# el_de_nosotros.net
KiCad netlist of a schematic drawn in EAGLE
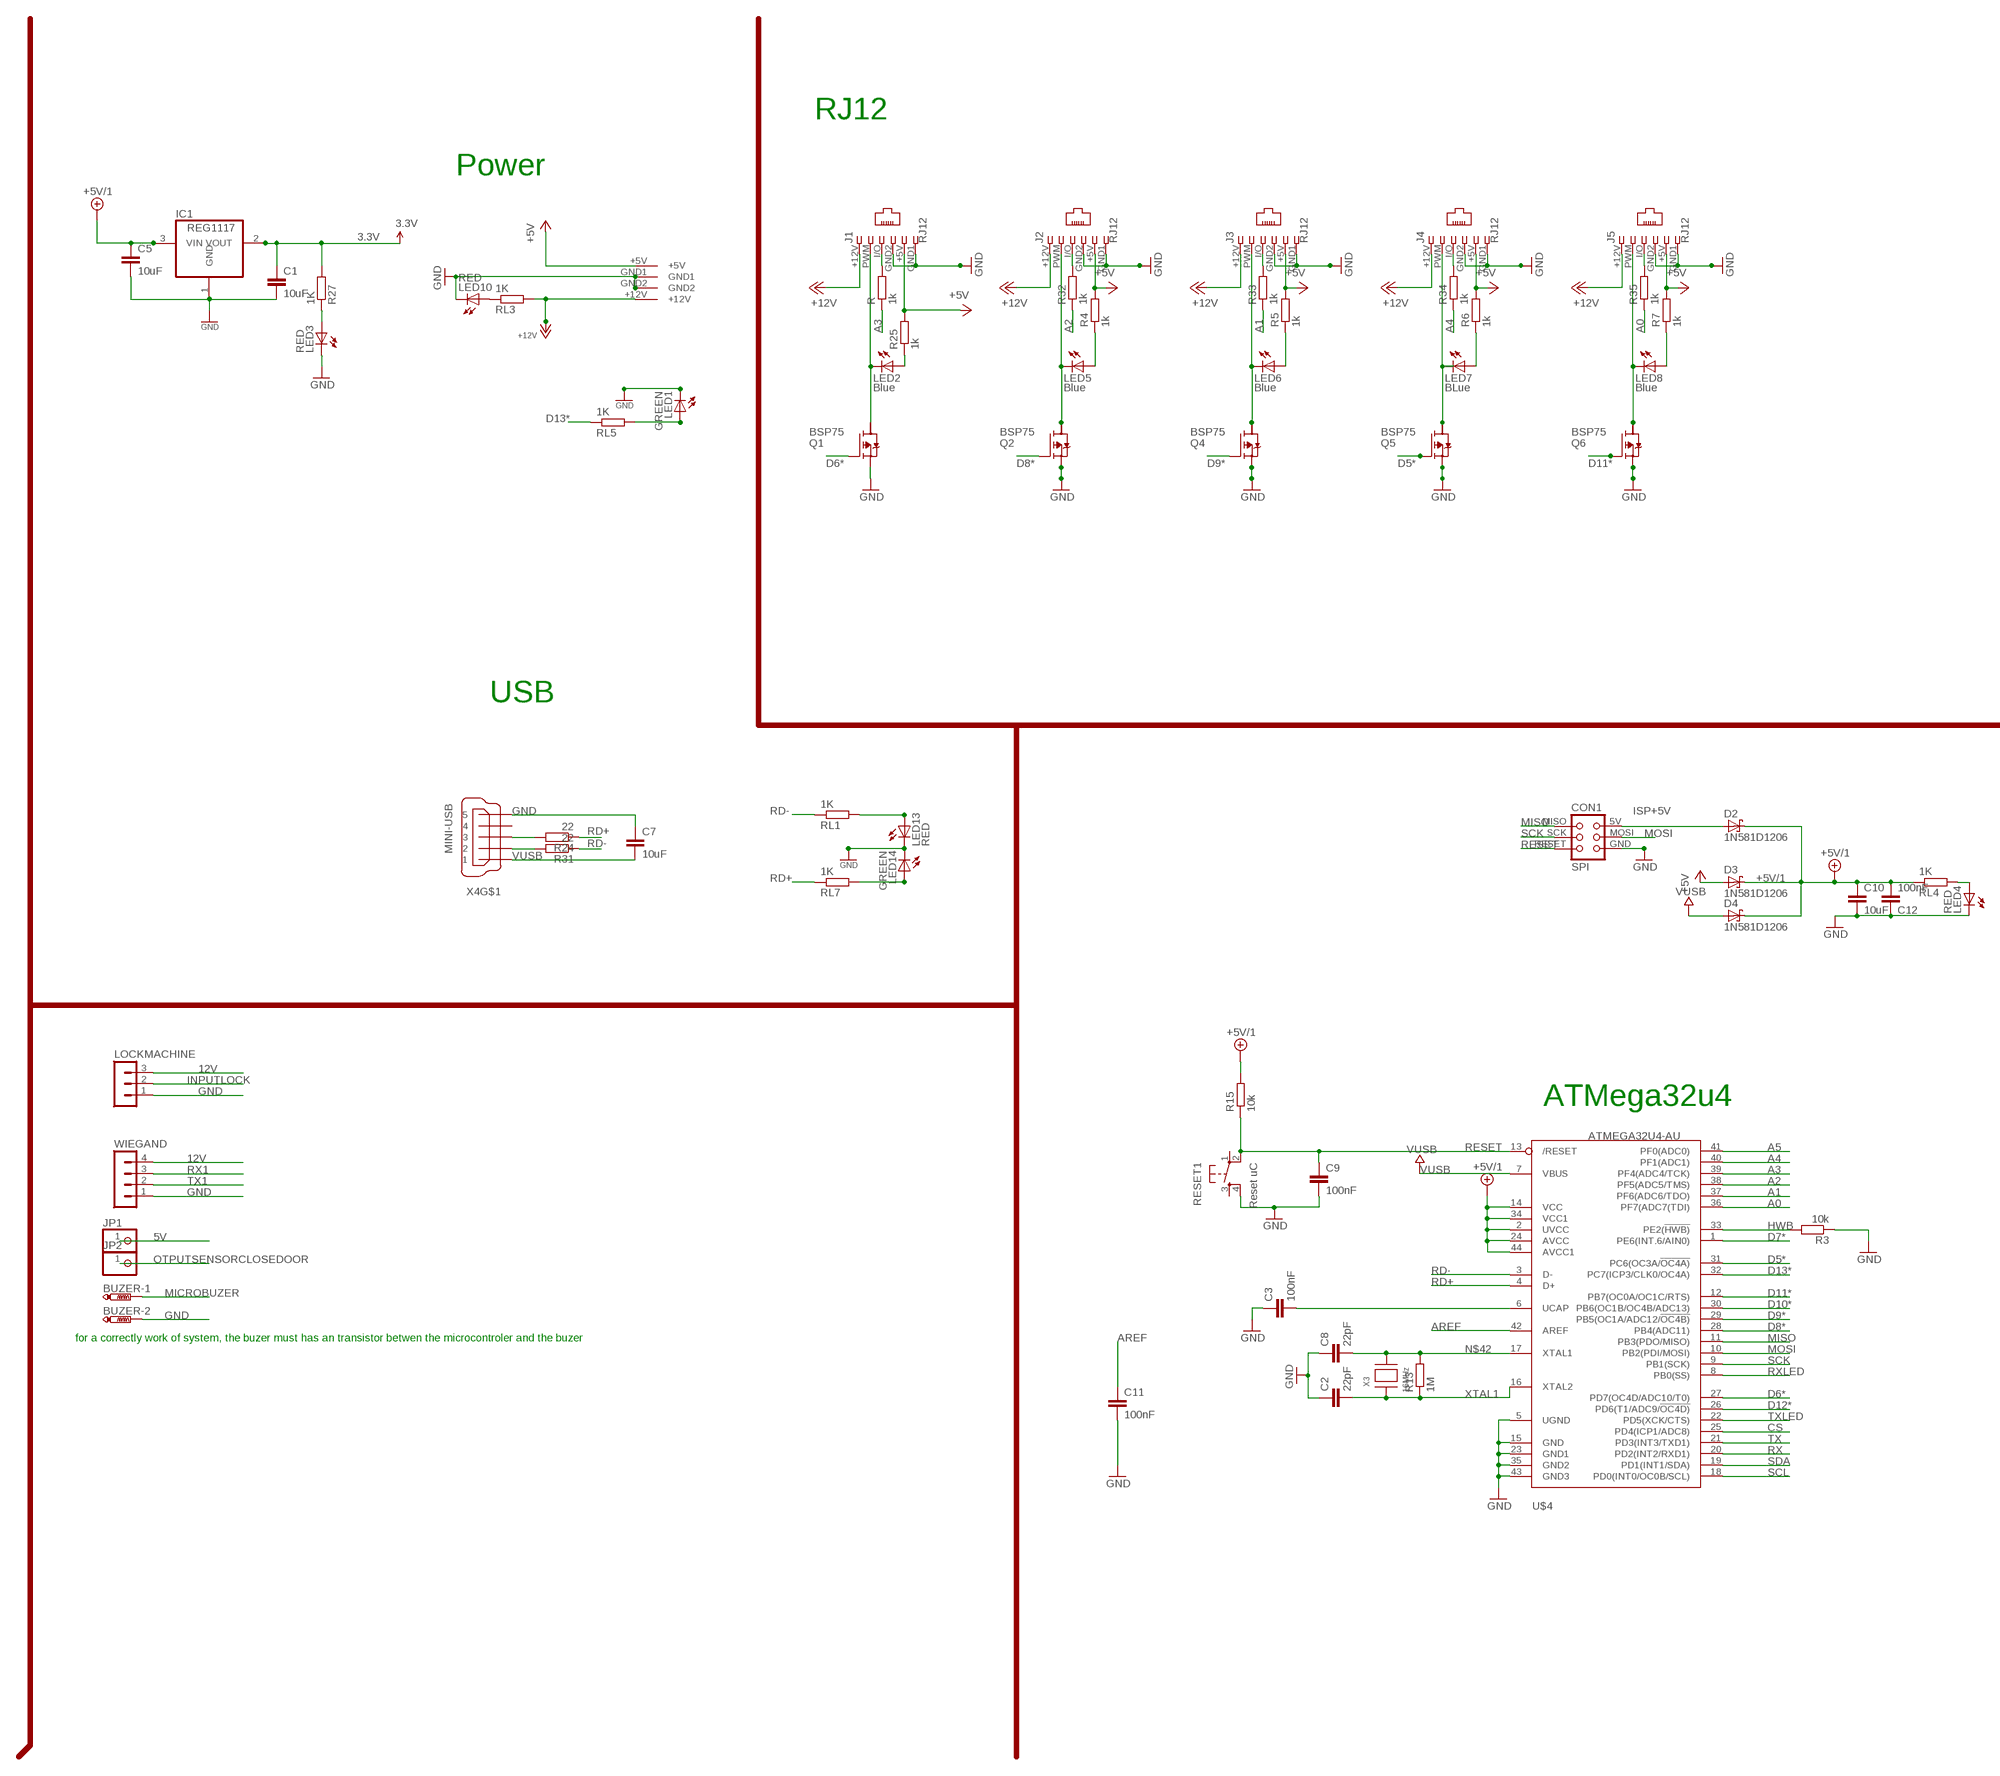
[diagram p0: schematic, sheet 1, part 1 of 2]
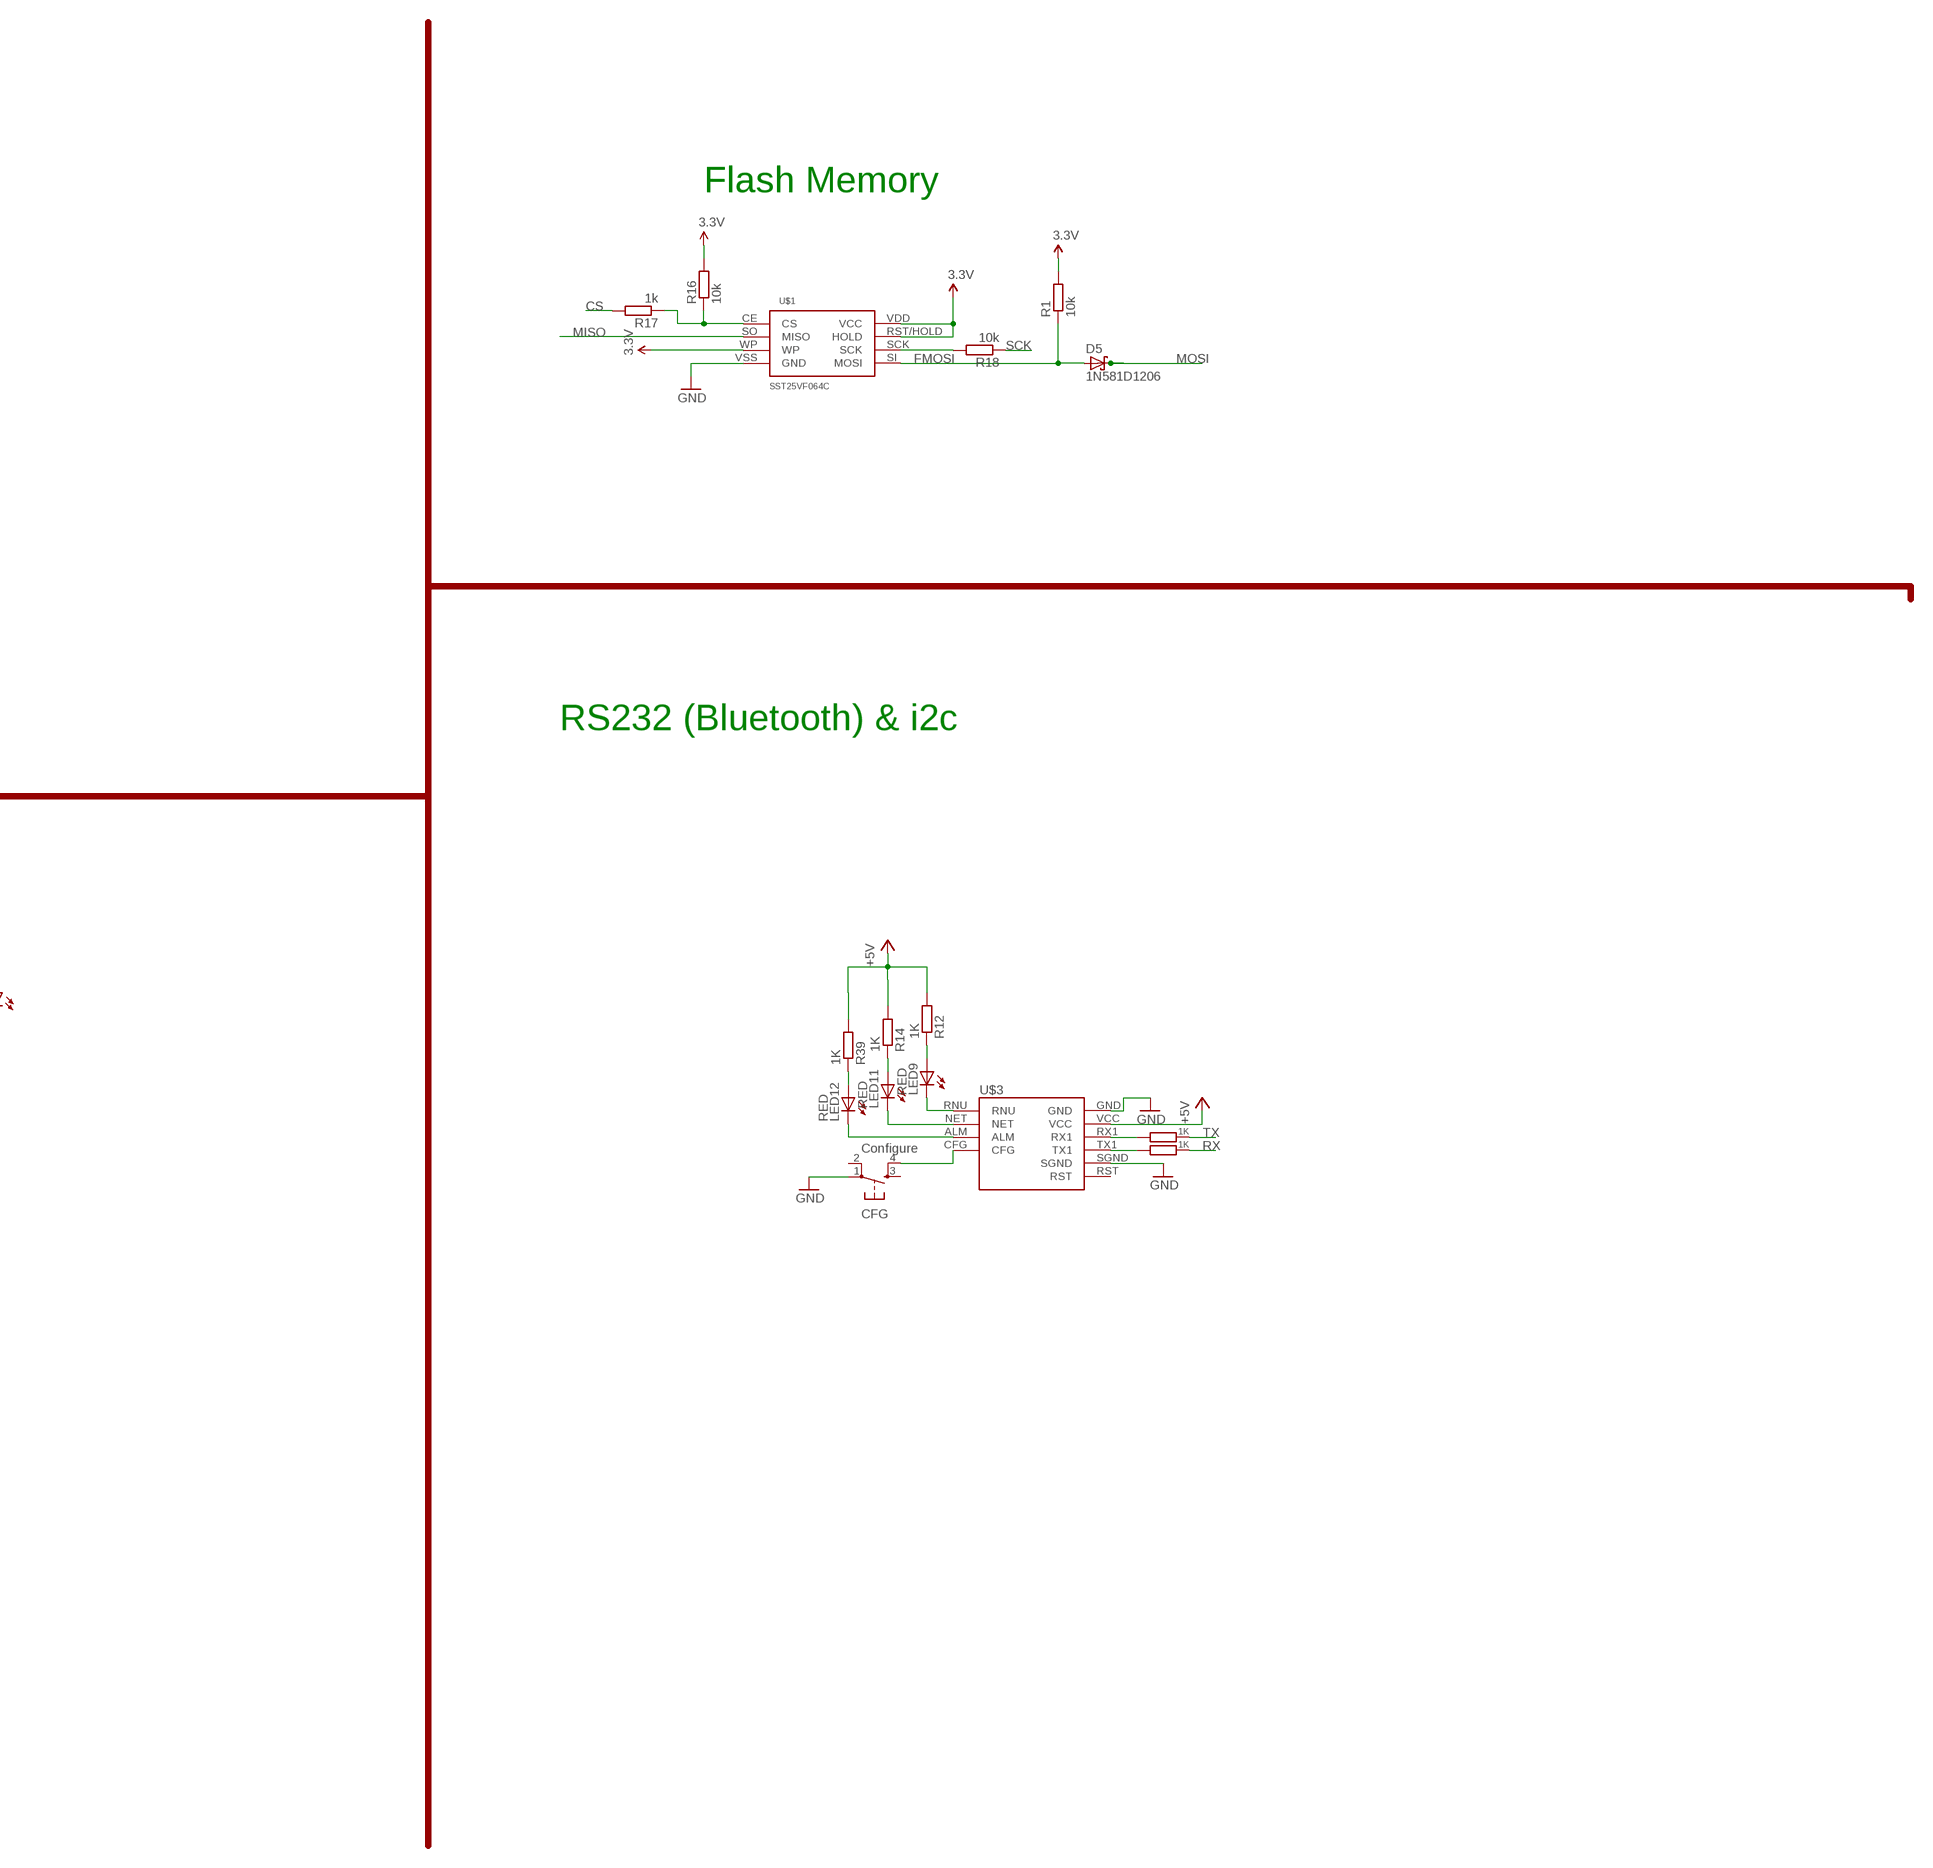
[diagram p1: schematic, sheet 1, part 2 of 2]

(export (version "E")
  (design (tool "Eeschema 10.0.6"))
  (components
    (comp (ref "BUZER")
      (value "PTR2")
      (footprint "eagle-import:P2-38-17")
      (libsource (lib "eagle-import") (part "PTR2"))
    )
    (comp (ref "C1")
      (value "10uF")
      (footprint "eagle-import:C1206")
      (libsource (lib "eagle-import") (part "C-EUC1206"))
    )
    (comp (ref "C2")
      (value "22pF")
      (footprint "eagle-import:C1206")
      (libsource (lib "eagle-import") (part "C-EUC1206"))
    )
    (comp (ref "C3")
      (value "100nF")
      (footprint "eagle-import:C1206")
      (libsource (lib "eagle-import") (part "C-EUC1206"))
    )
    (comp (ref "C5")
      (value "10uF")
      (footprint "eagle-import:C1206")
      (libsource (lib "eagle-import") (part "C-EUC1206"))
    )
    (comp (ref "C7")
      (value "10uF")
      (footprint "eagle-import:C1206")
      (libsource (lib "eagle-import") (part "C-EUC1206"))
    )
    (comp (ref "C8")
      (value "22pF")
      (footprint "eagle-import:C1206")
      (libsource (lib "eagle-import") (part "C-EUC1206"))
    )
    (comp (ref "C9")
      (value "100nF")
      (footprint "eagle-import:C1206")
      (libsource (lib "eagle-import") (part "C-EUC1206"))
    )
    (comp (ref "C10")
      (value "10uF")
      (footprint "eagle-import:C1206")
      (libsource (lib "eagle-import") (part "C-EUC1206"))
    )
    (comp (ref "C11")
      (value "100nF")
      (footprint "eagle-import:C1206")
      (libsource (lib "eagle-import") (part "C-EUC1206"))
    )
    (comp (ref "C12")
      (value "100nF")
      (footprint "eagle-import:C1206")
      (libsource (lib "eagle-import") (part "C-EUC1206"))
    )
    (comp (ref "CFG")
      (value "Configure")
      (footprint "eagle-import:TACTILE_SWITCH_SMD")
      (libsource (lib "eagle-import") (part "TAC_SWITCHSMD"))
    )
    (comp (ref "CON1")
      (value "SPI")
      (footprint "eagle-import:TC2030-MCP-NL")
      (libsource (lib "eagle-import") (part "TINYISPT"))
    )
    (comp (ref "D2")
      (value "1N581D1206")
      (footprint "eagle-import:LED-1206")
      (libsource (lib "eagle-import") (part "1N581D1206"))
    )
    (comp (ref "D3")
      (value "1N581D1206")
      (footprint "eagle-import:LED-1206")
      (libsource (lib "eagle-import") (part "1N581D1206"))
    )
    (comp (ref "D4")
      (value "1N581D1206")
      (footprint "eagle-import:LED-1206")
      (libsource (lib "eagle-import") (part "1N581D1206"))
    )
    (comp (ref "D5")
      (value "1N581D1206")
      (footprint "eagle-import:LED-1206")
      (libsource (lib "eagle-import") (part "1N581D1206"))
    )
    (comp (ref "IC1")
      (value "REG1117")
      (footprint "eagle-import:SOT223")
      (libsource (lib "eagle-import") (part "REG1117"))
    )
    (comp (ref "J1")
      (value "RJ12")
      (footprint "eagle-import:RJ12-STRAIGHT")
      (libsource (lib "eagle-import") (part "RJ12STRAIGHT"))
    )
    (comp (ref "J2")
      (value "RJ12")
      (footprint "eagle-import:RJ12-STRAIGHT")
      (libsource (lib "eagle-import") (part "RJ12STRAIGHT"))
    )
    (comp (ref "J3")
      (value "RJ12")
      (footprint "eagle-import:RJ12-STRAIGHT")
      (libsource (lib "eagle-import") (part "RJ12STRAIGHT"))
    )
    (comp (ref "J4")
      (value "RJ12")
      (footprint "eagle-import:RJ12-STRAIGHT")
      (libsource (lib "eagle-import") (part "RJ12STRAIGHT"))
    )
    (comp (ref "J5")
      (value "RJ12")
      (footprint "eagle-import:RJ12-STRAIGHT")
      (libsource (lib "eagle-import") (part "RJ12STRAIGHT"))
    )
    (comp (ref "JP1")
      (value "PINHD-1X1")
      (footprint "eagle-import:1X01")
      (libsource (lib "eagle-import") (part "PINHD-1X1"))
    )
    (comp (ref "JP2")
      (value "PINHD-1X1")
      (footprint "eagle-import:1X01")
      (libsource (lib "eagle-import") (part "PINHD-1X1"))
    )
    (comp (ref "LED1")
      (value "GREEN")
      (footprint "eagle-import:CHIPLED_1206")
      (libsource (lib "eagle-import") (part "LEDCHIPLED_1206"))
    )
    (comp (ref "LED2")
      (value "Blue")
      (footprint "eagle-import:CHIPLED_1206")
      (libsource (lib "eagle-import") (part "LEDCHIPLED_1206"))
    )
    (comp (ref "LED3")
      (value "RED")
      (footprint "eagle-import:CHIPLED_1206")
      (libsource (lib "eagle-import") (part "LEDCHIPLED_1206"))
    )
    (comp (ref "LED4")
      (value "RED")
      (footprint "eagle-import:CHIPLED_1206")
      (libsource (lib "eagle-import") (part "LEDCHIPLED_1206"))
    )
    (comp (ref "LED5")
      (value "Blue")
      (footprint "eagle-import:CHIPLED_1206")
      (libsource (lib "eagle-import") (part "LEDCHIPLED_1206"))
    )
    (comp (ref "LED6")
      (value "Blue")
      (footprint "eagle-import:CHIPLED_1206")
      (libsource (lib "eagle-import") (part "LEDCHIPLED_1206"))
    )
    (comp (ref "LED7")
      (value "BLue")
      (footprint "eagle-import:CHIPLED_1206")
      (libsource (lib "eagle-import") (part "LEDCHIPLED_1206"))
    )
    (comp (ref "LED8")
      (value "Blue")
      (footprint "eagle-import:CHIPLED_1206")
      (libsource (lib "eagle-import") (part "LEDCHIPLED_1206"))
    )
    (comp (ref "LED9")
      (value "RED")
      (footprint "eagle-import:CHIPLED_1206")
      (libsource (lib "eagle-import") (part "LEDCHIPLED_1206"))
    )
    (comp (ref "LED10")
      (value "RED")
      (footprint "eagle-import:CHIPLED_1206")
      (libsource (lib "eagle-import") (part "LEDCHIPLED_1206"))
    )
    (comp (ref "LED11")
      (value "RED")
      (footprint "eagle-import:CHIPLED_1206")
      (libsource (lib "eagle-import") (part "LEDCHIPLED_1206"))
    )
    (comp (ref "LED12")
      (value "RED")
      (footprint "eagle-import:CHIPLED_1206")
      (libsource (lib "eagle-import") (part "LEDCHIPLED_1206"))
    )
    (comp (ref "LED13")
      (value "RED")
      (footprint "eagle-import:CHIPLED_1206")
      (libsource (lib "eagle-import") (part "LEDCHIPLED_1206"))
    )
    (comp (ref "LED14")
      (value "GREEN")
      (footprint "eagle-import:CHIPLED_1206")
      (libsource (lib "eagle-import") (part "LEDCHIPLED_1206"))
    )
    (comp (ref "LOCKMACHINE")
      (value "MA03-1")
      (footprint "eagle-import:MA03-1")
      (libsource (lib "eagle-import") (part "MA03-1"))
    )
    (comp (ref "Q1")
      (value "BSP75")
      (footprint "eagle-import:PG-SOT-223")
      (libsource (lib "eagle-import") (part "BSP613P"))
    )
    (comp (ref "Q2")
      (value "BSP75")
      (footprint "eagle-import:PG-SOT-223")
      (libsource (lib "eagle-import") (part "BSP613P"))
    )
    (comp (ref "Q4")
      (value "BSP75")
      (footprint "eagle-import:PG-SOT-223")
      (libsource (lib "eagle-import") (part "BSP613P"))
    )
    (comp (ref "Q5")
      (value "BSP75")
      (footprint "eagle-import:PG-SOT-223")
      (libsource (lib "eagle-import") (part "BSP613P"))
    )
    (comp (ref "Q6")
      (value "BSP75")
      (footprint "eagle-import:PG-SOT-223")
      (libsource (lib "eagle-import") (part "BSP613P"))
    )
    (comp (ref "R")
      (value "1k")
      (footprint "eagle-import:R0805")
      (libsource (lib "eagle-import") (part "R-EU_R0805"))
    )
    (comp (ref "R1")
      (value "10k")
      (footprint "eagle-import:R0805")
      (libsource (lib "eagle-import") (part "R-EU_R0805"))
    )
    (comp (ref "R3")
      (value "10k")
      (footprint "eagle-import:M0805")
      (libsource (lib "eagle-import") (part "resistor_R-EU_M0805"))
    )
    (comp (ref "R4")
      (value "1k")
      (footprint "eagle-import:R0805")
      (libsource (lib "eagle-import") (part "R-EU_R0805"))
    )
    (comp (ref "R5")
      (value "1k")
      (footprint "eagle-import:R0805")
      (libsource (lib "eagle-import") (part "R-EU_R0805"))
    )
    (comp (ref "R6")
      (value "1k")
      (footprint "eagle-import:R0805")
      (libsource (lib "eagle-import") (part "R-EU_R0805"))
    )
    (comp (ref "R7")
      (value "1k")
      (footprint "eagle-import:R0805")
      (libsource (lib "eagle-import") (part "R-EU_R0805"))
    )
    (comp (ref "R8")
      (value "1K")
      (footprint "eagle-import:R0805")
      (libsource (lib "eagle-import") (part "R-EU_R0805"))
    )
    (comp (ref "R11")
      (value "1K")
      (footprint "eagle-import:R0805")
      (libsource (lib "eagle-import") (part "R-EU_R0805"))
    )
    (comp (ref "R12")
      (value "1K")
      (footprint "eagle-import:R0805")
      (libsource (lib "eagle-import") (part "R-EU_R0805"))
    )
    (comp (ref "R13")
      (value "1M")
      (footprint "eagle-import:R1206")
      (libsource (lib "eagle-import") (part "R-EU_R1206"))
    )
    (comp (ref "R14")
      (value "1K")
      (footprint "eagle-import:R0805")
      (libsource (lib "eagle-import") (part "R-EU_R0805"))
    )
    (comp (ref "R15")
      (value "10k")
      (footprint "eagle-import:M0805")
      (libsource (lib "eagle-import") (part "resistor_R-EU_M0805"))
    )
    (comp (ref "R16")
      (value "10k")
      (footprint "eagle-import:R0805")
      (libsource (lib "eagle-import") (part "R-EU_R0805"))
    )
    (comp (ref "R17")
      (value "1k")
      (footprint "eagle-import:R0805")
      (libsource (lib "eagle-import") (part "R-EU_R0805"))
    )
    (comp (ref "R18")
      (value "10k")
      (footprint "eagle-import:R0805")
      (libsource (lib "eagle-import") (part "R-EU_R0805"))
    )
    (comp (ref "R24")
      (value "22")
      (footprint "eagle-import:M1206")
      (libsource (lib "eagle-import") (part "resistor_R-EU_M1206"))
    )
    (comp (ref "R25")
      (value "1k")
      (footprint "eagle-import:R0805")
      (libsource (lib "eagle-import") (part "R-EU_R0805"))
    )
    (comp (ref "R27")
      (value "1K")
      (footprint "eagle-import:R0805")
      (libsource (lib "eagle-import") (part "R-EU_R0805"))
    )
    (comp (ref "R31")
      (value "22")
      (footprint "eagle-import:M1206")
      (libsource (lib "eagle-import") (part "resistor_R-EU_M1206"))
    )
    (comp (ref "R32")
      (value "1k")
      (footprint "eagle-import:R0805")
      (libsource (lib "eagle-import") (part "R-EU_R0805"))
    )
    (comp (ref "R33")
      (value "1k")
      (footprint "eagle-import:R0805")
      (libsource (lib "eagle-import") (part "R-EU_R0805"))
    )
    (comp (ref "R34")
      (value "1k")
      (footprint "eagle-import:R0805")
      (libsource (lib "eagle-import") (part "R-EU_R0805"))
    )
    (comp (ref "R35")
      (value "1k")
      (footprint "eagle-import:R0805")
      (libsource (lib "eagle-import") (part "R-EU_R0805"))
    )
    (comp (ref "R39")
      (value "1K")
      (footprint "eagle-import:R0805")
      (libsource (lib "eagle-import") (part "R-EU_R0805"))
    )
    (comp (ref "RESET1")
      (value "Reset uC")
      (footprint "eagle-import:TACTILE_SWITCH_SMD")
      (libsource (lib "eagle-import") (part "TAC_SWITCHSMD"))
    )
    (comp (ref "RL1")
      (value "1K")
      (footprint "eagle-import:R0805")
      (libsource (lib "eagle-import") (part "R-EU_R0805"))
    )
    (comp (ref "RL3")
      (value "1K")
      (footprint "eagle-import:R0805")
      (libsource (lib "eagle-import") (part "R-EU_R0805"))
    )
    (comp (ref "RL4")
      (value "1K")
      (footprint "eagle-import:R0805")
      (libsource (lib "eagle-import") (part "resistor_R-EU_R0805"))
    )
    (comp (ref "RL5")
      (value "1K")
      (footprint "eagle-import:R0805")
      (libsource (lib "eagle-import") (part "R-EU_R0805"))
    )
    (comp (ref "RL7")
      (value "1K")
      (footprint "eagle-import:R0805")
      (libsource (lib "eagle-import") (part "R-EU_R0805"))
    )
    (comp (ref "U$1")
      (value "SST25VF064C")
      (footprint "eagle-import:SOIC_8-LEAD")
      (libsource (lib "eagle-import") (part "SST25VF064C"))
    )
    (comp (ref "U$3")
      (value "SZ05-ZIGBEE")
      (footprint "eagle-import:SZ05-ZIGBEE")
      (libsource (lib "eagle-import") (part "SZ05-ZIGBEE"))
    )
    (comp (ref "U$4")
      (value "ATMEGA32U4-AU")
      (footprint "eagle-import:TQFP44")
      (libsource (lib "eagle-import") (part "ATMEGA32U4-AU"))
    )
    (comp (ref "U$6")
      (value "KPJX-4S-S")
      (footprint "eagle-import:KPJX-4S-S")
      (libsource (lib "eagle-import") (part "KPJX-4S-S"))
    )
    (comp (ref "WIEGAND")
      (value "MA04-1")
      (footprint "eagle-import:MA04-1")
      (libsource (lib "eagle-import") (part "MA04-1"))
    )
    (comp (ref "X3")
      (value "16MHz")
      (footprint "eagle-import:NX6035")
      (libsource (lib "eagle-import") (part "XTALNX6035"))
    )
    (comp (ref "X4")
      (value "MINI-USB")
      (footprint "eagle-import:32005-201")
      (libsource (lib "eagle-import") (part "MINI-USB-SCHIELD-32005-201"))
    )
  )
  (nets
    (net (code "1") (name "+5V") (class "Default")
      (node (ref "D3") (pin "A") (pinfunction "A_A") (pintype "passive"))
      (node (ref "J1") (pin "+5V") (pinfunction "5_+5V") (pintype "bidirectional"))
      (node (ref "J2") (pin "+5V") (pinfunction "5_+5V") (pintype "bidirectional"))
      (node (ref "J3") (pin "+5V") (pinfunction "5_+5V") (pintype "bidirectional"))
      (node (ref "J4") (pin "+5V") (pinfunction "5_+5V") (pintype "bidirectional"))
      (node (ref "J5") (pin "+5V") (pinfunction "5_+5V") (pintype "bidirectional"))
      (node (ref "R12") (pin "2") (pinfunction "2_2") (pintype "passive"))
      (node (ref "R14") (pin "2") (pinfunction "2_2") (pintype "passive"))
      (node (ref "R25") (pin "2") (pinfunction "2_2") (pintype "passive"))
      (node (ref "R39") (pin "2") (pinfunction "2_2") (pintype "passive"))
      (node (ref "R4") (pin "2") (pinfunction "2_2") (pintype "passive"))
      (node (ref "R5") (pin "2") (pinfunction "2_2") (pintype "passive"))
      (node (ref "R6") (pin "2") (pinfunction "2_2") (pintype "passive"))
      (node (ref "R7") (pin "2") (pinfunction "2_2") (pintype "passive"))
      (node (ref "U$3") (pin "VCC") (pinfunction "VCC_VCC") (pintype "bidirectional"))
      (node (ref "U$6") (pin "+5V") (pinfunction "+5V_+5V") (pintype "power_in"))
    )
    (net (code "2") (name "+5V{slash}1") (class "Default")
      (node (ref "C10") (pin "1") (pinfunction "1_1") (pintype "passive"))
      (node (ref "C12") (pin "2") (pinfunction "2_2") (pintype "passive"))
      (node (ref "C5") (pin "1") (pinfunction "1_1") (pintype "passive"))
      (node (ref "D2") (pin "C") (pinfunction "C_C") (pintype "passive"))
      (node (ref "D3") (pin "C") (pinfunction "C_C") (pintype "passive"))
      (node (ref "D4") (pin "C") (pinfunction "C_C") (pintype "passive"))
      (node (ref "IC1") (pin "3") (pinfunction "VIN_3") (pintype "input"))
      (node (ref "R15") (pin "2") (pinfunction "2_2") (pintype "passive"))
      (node (ref "RL4") (pin "1") (pinfunction "1_1") (pintype "passive"))
      (node (ref "U$4") (pin "14") (pinfunction "VCC_14") (pintype "bidirectional"))
      (node (ref "U$4") (pin "2") (pinfunction "UVCC_2") (pintype "bidirectional"))
      (node (ref "U$4") (pin "24") (pinfunction "AVCC_24") (pintype "bidirectional"))
      (node (ref "U$4") (pin "34") (pinfunction "VCC1_34") (pintype "bidirectional"))
      (node (ref "U$4") (pin "44") (pinfunction "AVCC1_44") (pintype "bidirectional"))
    )
    (net (code "3") (name "+12V") (class "Default")
      (node (ref "J1") (pin "+12V") (pinfunction "1_+12V") (pintype "bidirectional"))
      (node (ref "J2") (pin "+12V") (pinfunction "1_+12V") (pintype "bidirectional"))
      (node (ref "J3") (pin "+12V") (pinfunction "1_+12V") (pintype "bidirectional"))
      (node (ref "J4") (pin "+12V") (pinfunction "1_+12V") (pintype "bidirectional"))
      (node (ref "J5") (pin "+12V") (pinfunction "1_+12V") (pintype "bidirectional"))
      (node (ref "RL3") (pin "2") (pinfunction "2_2") (pintype "passive"))
      (node (ref "U$6") (pin "+12V") (pinfunction "+12V_+12V") (pintype "power_in"))
    )
    (net (code "4") (name "/5V") (class "Default")
      (node (ref "JP1") (pin "1") (pinfunction "1_1") (pintype "passive"))
    )
    (net (code "5") (name "/12V") (class "Default")
      (node (ref "LOCKMACHINE") (pin "3") (pinfunction "3_3") (pintype "passive"))
      (node (ref "WIEGAND") (pin "4") (pinfunction "4_4") (pintype "passive"))
    )
    (net (code "6") (name "/A0") (class "Default")
      (node (ref "R35") (pin "1") (pinfunction "1_1") (pintype "passive"))
      (node (ref "U$4") (pin "36") (pinfunction "PF7(ADC7(TDI)_36") (pintype "bidirectional"))
    )
    (net (code "7") (name "/A1") (class "Default")
      (node (ref "R33") (pin "1") (pinfunction "1_1") (pintype "passive"))
      (node (ref "U$4") (pin "37") (pinfunction "PF6(ADC6/TDO)_37") (pintype "bidirectional"))
    )
    (net (code "8") (name "/A2") (class "Default")
      (node (ref "R32") (pin "1") (pinfunction "1_1") (pintype "passive"))
      (node (ref "U$4") (pin "38") (pinfunction "PF5(ADC5/TMS)_38") (pintype "bidirectional"))
    )
    (net (code "9") (name "/A3") (class "Default")
      (node (ref "R") (pin "1") (pinfunction "1_1") (pintype "passive"))
      (node (ref "U$4") (pin "39") (pinfunction "PF4(ADC4/TCK)_39") (pintype "bidirectional"))
    )
    (net (code "10") (name "/A4") (class "Default")
      (node (ref "R34") (pin "1") (pinfunction "1_1") (pintype "passive"))
      (node (ref "U$4") (pin "40") (pinfunction "PF1(ADC1)_40") (pintype "bidirectional"))
    )
    (net (code "11") (name "/A5") (class "Default")
      (node (ref "U$4") (pin "41") (pinfunction "PF0(ADC0)_41") (pintype "bidirectional"))
    )
    (net (code "12") (name "/AREF") (class "Default")
      (node (ref "C11") (pin "1") (pinfunction "1_1") (pintype "passive"))
      (node (ref "U$4") (pin "42") (pinfunction "AREF_42") (pintype "bidirectional"))
    )
    (net (code "13") (name "/CS") (class "Default")
      (node (ref "R17") (pin "2") (pinfunction "2_2") (pintype "passive"))
      (node (ref "U$4") (pin "25") (pinfunction "PD4(ICP1/ADC8)_25") (pintype "bidirectional"))
    )
    (net (code "14") (name "/D5*") (class "Default")
      (node (ref "Q5") (pin "1") (pinfunction "G_1") (pintype "passive"))
      (node (ref "U$4") (pin "31") (pinfunction "PC6(OC3A/~{OC4A})_31") (pintype "bidirectional"))
    )
    (net (code "15") (name "/D6*") (class "Default")
      (node (ref "Q1") (pin "1") (pinfunction "G_1") (pintype "passive"))
      (node (ref "U$4") (pin "27") (pinfunction "PD7(OC4D/ADC10/T0)_27") (pintype "bidirectional"))
    )
    (net (code "16") (name "/D7*") (class "Default")
      (node (ref "U$4") (pin "1") (pinfunction "PE6(INT.6/AIN0)_1") (pintype "bidirectional"))
    )
    (net (code "17") (name "/D8*") (class "Default")
      (node (ref "Q2") (pin "1") (pinfunction "G_1") (pintype "passive"))
      (node (ref "U$4") (pin "28") (pinfunction "PB4(ADC11)_28") (pintype "bidirectional"))
    )
    (net (code "18") (name "/D9*") (class "Default")
      (node (ref "Q4") (pin "1") (pinfunction "G_1") (pintype "passive"))
      (node (ref "U$4") (pin "29") (pinfunction "PB5(OC1A/ADC12/~{OC4B})_29") (pintype "bidirectional"))
    )
    (net (code "19") (name "/D10*") (class "Default")
      (node (ref "U$4") (pin "30") (pinfunction "PB6(OC1B/OC4B/ADC13)_30") (pintype "bidirectional"))
    )
    (net (code "20") (name "/D11*") (class "Default")
      (node (ref "Q6") (pin "1") (pinfunction "G_1") (pintype "passive"))
      (node (ref "U$4") (pin "12") (pinfunction "PB7(OC0A/OC1C/RTS)_12") (pintype "bidirectional"))
    )
    (net (code "21") (name "/D12*") (class "Default")
      (node (ref "U$4") (pin "26") (pinfunction "PD6(T1/ADC9/~{OC4D})_26") (pintype "bidirectional"))
    )
    (net (code "22") (name "/D13*") (class "Default")
      (node (ref "RL5") (pin "1") (pinfunction "1_1") (pintype "passive"))
      (node (ref "U$4") (pin "32") (pinfunction "PC7(ICP3/CLK0/OC4A)_32") (pintype "bidirectional"))
    )
    (net (code "23") (name "/FMOSI") (class "Default")
      (node (ref "D5") (pin "A") (pinfunction "A_A") (pintype "passive"))
      (node (ref "R1") (pin "1") (pinfunction "1_1") (pintype "passive"))
      (node (ref "U$1") (pin "SI") (pinfunction "MOSI_SI") (pintype "bidirectional"))
    )
    (net (code "24") (name "/HWB") (class "Default")
      (node (ref "R3") (pin "2") (pinfunction "2_2") (pintype "passive"))
      (node (ref "U$4") (pin "33") (pinfunction "PE2(~{HWB})_33") (pintype "bidirectional"))
    )
    (net (code "25") (name "/INPUTLOCK") (class "Default")
      (node (ref "LOCKMACHINE") (pin "2") (pinfunction "2_2") (pintype "passive"))
    )
    (net (code "26") (name "/ISP+5V") (class "Default")
      (node (ref "CON1") (pin "5V") (pinfunction "VCC_5V") (pintype "passive"))
      (node (ref "D2") (pin "A") (pinfunction "A_A") (pintype "passive"))
    )
    (net (code "27") (name "/MICROBUZER") (class "Default")
      (node (ref "BUZER") (pin "TP-1") (pinfunction "TP_TP-1") (pintype "input"))
    )
    (net (code "28") (name "/MISO") (class "Default")
      (node (ref "CON1") (pin "MISO") (pinfunction "MISO_MISO") (pintype "passive"))
      (node (ref "U$1") (pin "SO") (pinfunction "MISO_SO") (pintype "bidirectional"))
      (node (ref "U$4") (pin "11") (pinfunction "PB3(PDO/MISO)_11") (pintype "bidirectional"))
    )
    (net (code "29") (name "/MOSI") (class "Default")
      (node (ref "CON1") (pin "MOSI") (pinfunction "MOSI_MOSI") (pintype "passive"))
      (node (ref "D5") (pin "C") (pinfunction "C_C") (pintype "passive"))
      (node (ref "U$4") (pin "10") (pinfunction "PB2(PDI/MOSI)_10") (pintype "bidirectional"))
    )
    (net (code "30") (name "/N$42") (class "Default")
      (node (ref "C8") (pin "2") (pinfunction "2_2") (pintype "passive"))
      (node (ref "R13") (pin "2") (pinfunction "2_2") (pintype "passive"))
      (node (ref "U$4") (pin "17") (pinfunction "XTAL1_17") (pintype "bidirectional"))
      (node (ref "X3") (pin "P$2") (pinfunction "P$2_P$2") (pintype "bidirectional"))
    )
    (net (code "31") (name "/OTPUTSENSORCLOSEDOOR") (class "Default")
      (node (ref "JP2") (pin "1") (pinfunction "1_1") (pintype "passive"))
    )
    (net (code "32") (name "/RD+") (class "Default")
      (node (ref "R24") (pin "1") (pinfunction "1_1") (pintype "passive"))
      (node (ref "RL7") (pin "1") (pinfunction "1_1") (pintype "passive"))
      (node (ref "U$4") (pin "4") (pinfunction "D+_4") (pintype "bidirectional"))
    )
    (net (code "33") (name "/RD-") (class "Default")
      (node (ref "R31") (pin "1") (pinfunction "1_1") (pintype "passive"))
      (node (ref "RL1") (pin "1") (pinfunction "1_1") (pintype "passive"))
      (node (ref "U$4") (pin "3") (pinfunction "D-_3") (pintype "bidirectional"))
    )
    (net (code "34") (name "/RESET") (class "Default")
      (node (ref "C9") (pin "1") (pinfunction "1_1") (pintype "passive"))
      (node (ref "CON1") (pin "RESET") (pinfunction "RESET_RESET") (pintype "passive"))
      (node (ref "R15") (pin "1") (pinfunction "1_1") (pintype "passive"))
      (node (ref "RESET1") (pin "2") (pinfunction "2_2") (pintype "passive"))
      (node (ref "U$4") (pin "13") (pinfunction "/RESET_13") (pintype "bidirectional"))
    )
    (net (code "35") (name "/RX") (class "Default")
      (node (ref "R8") (pin "1") (pinfunction "1_1") (pintype "passive"))
      (node (ref "U$4") (pin "20") (pinfunction "PD2(INT2/RXD1)_20") (pintype "bidirectional"))
    )
    (net (code "36") (name "/RX1") (class "Default")
      (node (ref "WIEGAND") (pin "3") (pinfunction "3_3") (pintype "passive"))
    )
    (net (code "37") (name "/RXLED") (class "Default")
      (node (ref "U$4") (pin "8") (pinfunction "PB0(SS)_8") (pintype "bidirectional"))
    )
    (net (code "38") (name "/SCK") (class "Default")
      (node (ref "CON1") (pin "SCK") (pinfunction "SCK_SCK") (pintype "passive"))
      (node (ref "R18") (pin "1") (pinfunction "1_1") (pintype "passive"))
      (node (ref "U$4") (pin "9") (pinfunction "PB1(SCK)_9") (pintype "bidirectional"))
    )
    (net (code "39") (name "/SCL") (class "Default")
      (node (ref "U$4") (pin "18") (pinfunction "PD0(INT0/OC0B/SCL)_18") (pintype "bidirectional"))
    )
    (net (code "40") (name "/SDA") (class "Default")
      (node (ref "U$4") (pin "19") (pinfunction "PD1(INT1/SDA)_19") (pintype "bidirectional"))
    )
    (net (code "41") (name "/TX") (class "Default")
      (node (ref "R11") (pin "1") (pinfunction "1_1") (pintype "passive"))
      (node (ref "U$4") (pin "21") (pinfunction "PD3(INT3/TXD1)_21") (pintype "bidirectional"))
    )
    (net (code "42") (name "/TX1") (class "Default")
      (node (ref "WIEGAND") (pin "2") (pinfunction "2_2") (pintype "passive"))
    )
    (net (code "43") (name "/TXLED") (class "Default")
      (node (ref "U$4") (pin "22") (pinfunction "PD5(XCK/CTS)_22") (pintype "bidirectional"))
    )
    (net (code "44") (name "/XTAL1") (class "Default")
      (node (ref "C2") (pin "2") (pinfunction "2_2") (pintype "passive"))
      (node (ref "R13") (pin "1") (pinfunction "1_1") (pintype "passive"))
      (node (ref "U$4") (pin "16") (pinfunction "XTAL2_16") (pintype "bidirectional"))
      (node (ref "X3") (pin "P$1") (pinfunction "P$1_P$1") (pintype "bidirectional"))
    )
    (net (code "45") (name "3.3V") (class "Default")
      (node (ref "C1") (pin "1") (pinfunction "1_1") (pintype "passive"))
      (node (ref "IC1") (pin "2") (pinfunction "VOUT_2") (pintype "output"))
      (node (ref "R1") (pin "2") (pinfunction "2_2") (pintype "passive"))
      (node (ref "R16") (pin "2") (pinfunction "2_2") (pintype "passive"))
      (node (ref "R27") (pin "2") (pinfunction "2_2") (pintype "passive"))
      (node (ref "U$1") (pin "RST/HOLD") (pinfunction "HOLD_RST/HOLD") (pintype "bidirectional"))
      (node (ref "U$1") (pin "VDD") (pinfunction "VCC_VDD") (pintype "bidirectional"))
      (node (ref "U$1") (pin "WP") (pinfunction "WP_WP") (pintype "bidirectional"))
    )
    (net (code "46") (name "GND") (class "Default")
      (node (ref "BUZER") (pin "TP-2") (pinfunction "TP_TP-2") (pintype "input"))
      (node (ref "C1") (pin "2") (pinfunction "2_2") (pintype "passive"))
      (node (ref "C10") (pin "2") (pinfunction "2_2") (pintype "passive"))
      (node (ref "C11") (pin "2") (pinfunction "2_2") (pintype "passive"))
      (node (ref "C12") (pin "1") (pinfunction "1_1") (pintype "passive"))
      (node (ref "C2") (pin "1") (pinfunction "1_1") (pintype "passive"))
      (node (ref "C3") (pin "1") (pinfunction "1_1") (pintype "passive"))
      (node (ref "C5") (pin "2") (pinfunction "2_2") (pintype "passive"))
      (node (ref "C7") (pin "1") (pinfunction "1_1") (pintype "passive"))
      (node (ref "C8") (pin "1") (pinfunction "1_1") (pintype "passive"))
      (node (ref "C9") (pin "2") (pinfunction "2_2") (pintype "passive"))
      (node (ref "CFG") (pin "1") (pinfunction "1_1") (pintype "passive"))
      (node (ref "CON1") (pin "GND") (pinfunction "GND_GND") (pintype "passive"))
      (node (ref "IC1") (pin "1") (pinfunction "GND_1") (pintype "power_in"))
      (node (ref "J1") (pin "GND1") (pinfunction "6_GND1") (pintype "bidirectional"))
      (node (ref "J1") (pin "GND2") (pinfunction "4_GND2") (pintype "bidirectional"))
      (node (ref "J2") (pin "GND1") (pinfunction "6_GND1") (pintype "bidirectional"))
      (node (ref "J2") (pin "GND2") (pinfunction "4_GND2") (pintype "bidirectional"))
      (node (ref "J3") (pin "GND1") (pinfunction "6_GND1") (pintype "bidirectional"))
      (node (ref "J3") (pin "GND2") (pinfunction "4_GND2") (pintype "bidirectional"))
      (node (ref "J4") (pin "GND1") (pinfunction "6_GND1") (pintype "bidirectional"))
      (node (ref "J4") (pin "GND2") (pinfunction "4_GND2") (pintype "bidirectional"))
      (node (ref "J5") (pin "GND1") (pinfunction "6_GND1") (pintype "bidirectional"))
      (node (ref "J5") (pin "GND2") (pinfunction "4_GND2") (pintype "bidirectional"))
      (node (ref "LED1") (pin "C") (pinfunction "C_C") (pintype "passive"))
      (node (ref "LED10") (pin "C") (pinfunction "C_C") (pintype "passive"))
      (node (ref "LED13") (pin "C") (pinfunction "C_C") (pintype "passive"))
      (node (ref "LED14") (pin "C") (pinfunction "C_C") (pintype "passive"))
      (node (ref "LED3") (pin "C") (pinfunction "C_C") (pintype "passive"))
      (node (ref "LED4") (pin "C") (pinfunction "C_C") (pintype "passive"))
      (node (ref "LOCKMACHINE") (pin "1") (pinfunction "1_1") (pintype "passive"))
      (node (ref "Q1") (pin "3") (pinfunction "S_3") (pintype "passive"))
      (node (ref "Q2") (pin "3") (pinfunction "S_3") (pintype "passive"))
      (node (ref "Q4") (pin "3") (pinfunction "S_3") (pintype "passive"))
      (node (ref "Q5") (pin "3") (pinfunction "S_3") (pintype "passive"))
      (node (ref "Q6") (pin "3") (pinfunction "S_3") (pintype "passive"))
      (node (ref "R3") (pin "1") (pinfunction "1_1") (pintype "passive"))
      (node (ref "RESET1") (pin "4") (pinfunction "4_4") (pintype "passive"))
      (node (ref "U$1") (pin "VSS") (pinfunction "GND_VSS") (pintype "bidirectional"))
      (node (ref "U$3") (pin "GND") (pinfunction "GND_GND") (pintype "bidirectional"))
      (node (ref "U$3") (pin "SGND") (pinfunction "SGND_SGND") (pintype "bidirectional"))
      (node (ref "U$4") (pin "15") (pinfunction "GND_15") (pintype "bidirectional"))
      (node (ref "U$4") (pin "23") (pinfunction "GND1_23") (pintype "bidirectional"))
      (node (ref "U$4") (pin "35") (pinfunction "GND2_35") (pintype "bidirectional"))
      (node (ref "U$4") (pin "43") (pinfunction "GND3_43") (pintype "bidirectional"))
      (node (ref "U$4") (pin "5") (pinfunction "UGND_5") (pintype "bidirectional"))
      (node (ref "U$6") (pin "GND1") (pinfunction "GND1_GND1") (pintype "input"))
      (node (ref "U$6") (pin "GND2") (pinfunction "GND2_GND2") (pintype "input"))
      (node (ref "WIEGAND") (pin "1") (pinfunction "1_1") (pintype "passive"))
      (node (ref "X4") (pin "5") (pinfunction "5_5") (pintype "passive"))
    )
    (net (code "47") (name "Net-(CFG-Pad4)") (class "Default")
      (node (ref "CFG") (pin "4") (pinfunction "4_4") (pintype "passive"))
      (node (ref "U$3") (pin "CFG") (pinfunction "CFG_CFG") (pintype "bidirectional"))
    )
    (net (code "48") (name "Net-(J1-2)") (class "Default")
      (node (ref "J1") (pin "PWM") (pinfunction "2_PWM") (pintype "bidirectional"))
      (node (ref "LED2") (pin "C") (pinfunction "C_C") (pintype "passive"))
      (node (ref "Q1") (pin "2") (pinfunction "D_2") (pintype "passive"))
    )
    (net (code "49") (name "Net-(J1-3)") (class "Default")
      (node (ref "J1") (pin "I/O") (pinfunction "3_I/O") (pintype "bidirectional"))
      (node (ref "R") (pin "2") (pinfunction "2_2") (pintype "passive"))
    )
    (net (code "50") (name "Net-(J2-2)") (class "Default")
      (node (ref "J2") (pin "PWM") (pinfunction "2_PWM") (pintype "bidirectional"))
      (node (ref "LED5") (pin "C") (pinfunction "C_C") (pintype "passive"))
      (node (ref "Q2") (pin "2") (pinfunction "D_2") (pintype "passive"))
    )
    (net (code "51") (name "Net-(J2-3)") (class "Default")
      (node (ref "J2") (pin "I/O") (pinfunction "3_I/O") (pintype "bidirectional"))
      (node (ref "R32") (pin "2") (pinfunction "2_2") (pintype "passive"))
    )
    (net (code "52") (name "Net-(J3-2)") (class "Default")
      (node (ref "J3") (pin "PWM") (pinfunction "2_PWM") (pintype "bidirectional"))
      (node (ref "LED6") (pin "C") (pinfunction "C_C") (pintype "passive"))
      (node (ref "Q4") (pin "2") (pinfunction "D_2") (pintype "passive"))
    )
    (net (code "53") (name "Net-(J3-3)") (class "Default")
      (node (ref "J3") (pin "I/O") (pinfunction "3_I/O") (pintype "bidirectional"))
      (node (ref "R33") (pin "2") (pinfunction "2_2") (pintype "passive"))
    )
    (net (code "54") (name "Net-(J4-2)") (class "Default")
      (node (ref "J4") (pin "PWM") (pinfunction "2_PWM") (pintype "bidirectional"))
      (node (ref "LED7") (pin "C") (pinfunction "C_C") (pintype "passive"))
      (node (ref "Q5") (pin "2") (pinfunction "D_2") (pintype "passive"))
    )
    (net (code "55") (name "Net-(J4-3)") (class "Default")
      (node (ref "J4") (pin "I/O") (pinfunction "3_I/O") (pintype "bidirectional"))
      (node (ref "R34") (pin "2") (pinfunction "2_2") (pintype "passive"))
    )
    (net (code "56") (name "Net-(J5-2)") (class "Default")
      (node (ref "J5") (pin "PWM") (pinfunction "2_PWM") (pintype "bidirectional"))
      (node (ref "LED8") (pin "C") (pinfunction "C_C") (pintype "passive"))
      (node (ref "Q6") (pin "2") (pinfunction "D_2") (pintype "passive"))
    )
    (net (code "57") (name "Net-(J5-3)") (class "Default")
      (node (ref "J5") (pin "I/O") (pinfunction "3_I/O") (pintype "bidirectional"))
      (node (ref "R35") (pin "2") (pinfunction "2_2") (pintype "passive"))
    )
    (net (code "58") (name "Net-(LED1-PadA)") (class "Default")
      (node (ref "LED1") (pin "A") (pinfunction "A_A") (pintype "passive"))
      (node (ref "RL5") (pin "2") (pinfunction "2_2") (pintype "passive"))
    )
    (net (code "59") (name "Net-(LED2-PadA)") (class "Default")
      (node (ref "LED2") (pin "A") (pinfunction "A_A") (pintype "passive"))
      (node (ref "R25") (pin "1") (pinfunction "1_1") (pintype "passive"))
    )
    (net (code "60") (name "Net-(LED3-PadA)") (class "Default")
      (node (ref "LED3") (pin "A") (pinfunction "A_A") (pintype "passive"))
      (node (ref "R27") (pin "1") (pinfunction "1_1") (pintype "passive"))
    )
    (net (code "61") (name "Net-(LED4-PadA)") (class "Default")
      (node (ref "LED4") (pin "A") (pinfunction "A_A") (pintype "passive"))
      (node (ref "RL4") (pin "2") (pinfunction "2_2") (pintype "passive"))
    )
    (net (code "62") (name "Net-(LED5-PadA)") (class "Default")
      (node (ref "LED5") (pin "A") (pinfunction "A_A") (pintype "passive"))
      (node (ref "R4") (pin "1") (pinfunction "1_1") (pintype "passive"))
    )
    (net (code "63") (name "Net-(LED6-PadA)") (class "Default")
      (node (ref "LED6") (pin "A") (pinfunction "A_A") (pintype "passive"))
      (node (ref "R5") (pin "1") (pinfunction "1_1") (pintype "passive"))
    )
    (net (code "64") (name "Net-(LED7-PadA)") (class "Default")
      (node (ref "LED7") (pin "A") (pinfunction "A_A") (pintype "passive"))
      (node (ref "R6") (pin "1") (pinfunction "1_1") (pintype "passive"))
    )
    (net (code "65") (name "Net-(LED8-PadA)") (class "Default")
      (node (ref "LED8") (pin "A") (pinfunction "A_A") (pintype "passive"))
      (node (ref "R7") (pin "1") (pinfunction "1_1") (pintype "passive"))
    )
    (net (code "66") (name "Net-(LED9-PadA)") (class "Default")
      (node (ref "LED9") (pin "A") (pinfunction "A_A") (pintype "passive"))
      (node (ref "R12") (pin "1") (pinfunction "1_1") (pintype "passive"))
    )
    (net (code "67") (name "Net-(LED9-PadC)") (class "Default")
      (node (ref "LED9") (pin "C") (pinfunction "C_C") (pintype "passive"))
      (node (ref "U$3") (pin "RNU") (pinfunction "RNU_RNU") (pintype "bidirectional"))
    )
    (net (code "68") (name "Net-(LED10-PadA)") (class "Default")
      (node (ref "LED10") (pin "A") (pinfunction "A_A") (pintype "passive"))
      (node (ref "RL3") (pin "1") (pinfunction "1_1") (pintype "passive"))
    )
    (net (code "69") (name "Net-(LED11-PadA)") (class "Default")
      (node (ref "LED11") (pin "A") (pinfunction "A_A") (pintype "passive"))
      (node (ref "R14") (pin "1") (pinfunction "1_1") (pintype "passive"))
    )
    (net (code "70") (name "Net-(LED11-PadC)") (class "Default")
      (node (ref "LED11") (pin "C") (pinfunction "C_C") (pintype "passive"))
      (node (ref "U$3") (pin "NET") (pinfunction "NET_NET") (pintype "bidirectional"))
    )
    (net (code "71") (name "Net-(LED12-PadA)") (class "Default")
      (node (ref "LED12") (pin "A") (pinfunction "A_A") (pintype "passive"))
      (node (ref "R39") (pin "1") (pinfunction "1_1") (pintype "passive"))
    )
    (net (code "72") (name "Net-(LED12-PadC)") (class "Default")
      (node (ref "LED12") (pin "C") (pinfunction "C_C") (pintype "passive"))
      (node (ref "U$3") (pin "ALM") (pinfunction "ALM_ALM") (pintype "bidirectional"))
    )
    (net (code "73") (name "Net-(LED13-PadA)") (class "Default")
      (node (ref "LED13") (pin "A") (pinfunction "A_A") (pintype "passive"))
      (node (ref "RL1") (pin "2") (pinfunction "2_2") (pintype "passive"))
    )
    (net (code "74") (name "Net-(LED14-PadA)") (class "Default")
      (node (ref "LED14") (pin "A") (pinfunction "A_A") (pintype "passive"))
      (node (ref "RL7") (pin "2") (pinfunction "2_2") (pintype "passive"))
    )
    (net (code "75") (name "Net-(R8-Pad2)") (class "Default")
      (node (ref "R8") (pin "2") (pinfunction "2_2") (pintype "passive"))
      (node (ref "U$3") (pin "TX1") (pinfunction "TX1_TX1") (pintype "bidirectional"))
    )
    (net (code "76") (name "Net-(R11-Pad2)") (class "Default")
      (node (ref "R11") (pin "2") (pinfunction "2_2") (pintype "passive"))
      (node (ref "U$3") (pin "RX1") (pinfunction "RX1_RX1") (pintype "bidirectional"))
    )
    (net (code "77") (name "Net-(R18-Pad2)") (class "Default")
      (node (ref "R18") (pin "2") (pinfunction "2_2") (pintype "passive"))
      (node (ref "U$1") (pin "SCK") (pinfunction "SCK_SCK") (pintype "bidirectional"))
    )
    (net (code "78") (name "Net-(R24-Pad2)") (class "Default")
      (node (ref "R24") (pin "2") (pinfunction "2_2") (pintype "passive"))
      (node (ref "X4") (pin "3") (pinfunction "3_3") (pintype "passive"))
    )
    (net (code "79") (name "Net-(R31-Pad2)") (class "Default")
      (node (ref "R31") (pin "2") (pinfunction "2_2") (pintype "passive"))
      (node (ref "X4") (pin "2") (pinfunction "2_2") (pintype "passive"))
    )
    (net (code "80") (name "Net-(U$1-CS)") (class "Default")
      (node (ref "R16") (pin "1") (pinfunction "1_1") (pintype "passive"))
      (node (ref "R17") (pin "1") (pinfunction "1_1") (pintype "passive"))
      (node (ref "U$1") (pin "CE") (pinfunction "CS_CE") (pintype "bidirectional"))
    )
    (net (code "81") (name "Net-(U$4-UCAP)") (class "Default")
      (node (ref "C3") (pin "2") (pinfunction "2_2") (pintype "passive"))
      (node (ref "U$4") (pin "6") (pinfunction "UCAP_6") (pintype "bidirectional"))
    )
    (net (code "82") (name "VUSB") (class "Default")
      (node (ref "C7") (pin "2") (pinfunction "2_2") (pintype "passive"))
      (node (ref "D4") (pin "A") (pinfunction "A_A") (pintype "passive"))
      (node (ref "U$4") (pin "7") (pinfunction "VBUS_7") (pintype "bidirectional"))
      (node (ref "X4") (pin "1") (pinfunction "1_1") (pintype "passive"))
    )
    (net (code "83") (name "unconnected-(CFG-Pad2)") (class "Default")
      (node (ref "CFG") (pin "2") (pinfunction "2_2") (pintype "passive"))
    )
    (net (code "84") (name "unconnected-(CFG-Pad3)") (class "Default")
      (node (ref "CFG") (pin "3") (pinfunction "3_3") (pintype "passive"))
    )
    (net (code "85") (name "unconnected-(Q1-D-Pad4)") (class "Default")
      (node (ref "Q1") (pin "4") (pinfunction "D_4") (pintype "passive"))
    )
    (net (code "86") (name "unconnected-(Q2-D-Pad4)") (class "Default")
      (node (ref "Q2") (pin "4") (pinfunction "D_4") (pintype "passive"))
    )
    (net (code "87") (name "unconnected-(Q4-D-Pad4)") (class "Default")
      (node (ref "Q4") (pin "4") (pinfunction "D_4") (pintype "passive"))
    )
    (net (code "88") (name "unconnected-(Q5-D-Pad4)") (class "Default")
      (node (ref "Q5") (pin "4") (pinfunction "D_4") (pintype "passive"))
    )
    (net (code "89") (name "unconnected-(Q6-D-Pad4)") (class "Default")
      (node (ref "Q6") (pin "4") (pinfunction "D_4") (pintype "passive"))
    )
    (net (code "90") (name "unconnected-(RESET1-Pad1)") (class "Default")
      (node (ref "RESET1") (pin "1") (pinfunction "1_1") (pintype "passive"))
    )
    (net (code "91") (name "unconnected-(RESET1-Pad3)") (class "Default")
      (node (ref "RESET1") (pin "3") (pinfunction "3_3") (pintype "passive"))
    )
    (net (code "92") (name "unconnected-(U$3-PadRST)") (class "Default")
      (node (ref "U$3") (pin "RST") (pinfunction "RST_RST") (pintype "bidirectional"))
    )
    (net (code "93") (name "unconnected-(X4-Pad4)") (class "Default")
      (node (ref "X4") (pin "4") (pinfunction "4_4") (pintype "passive"))
    )
  )
)
